# lipo_charger_sense_nicolai.net
KiCad netlist of a schematic drawn in EAGLE
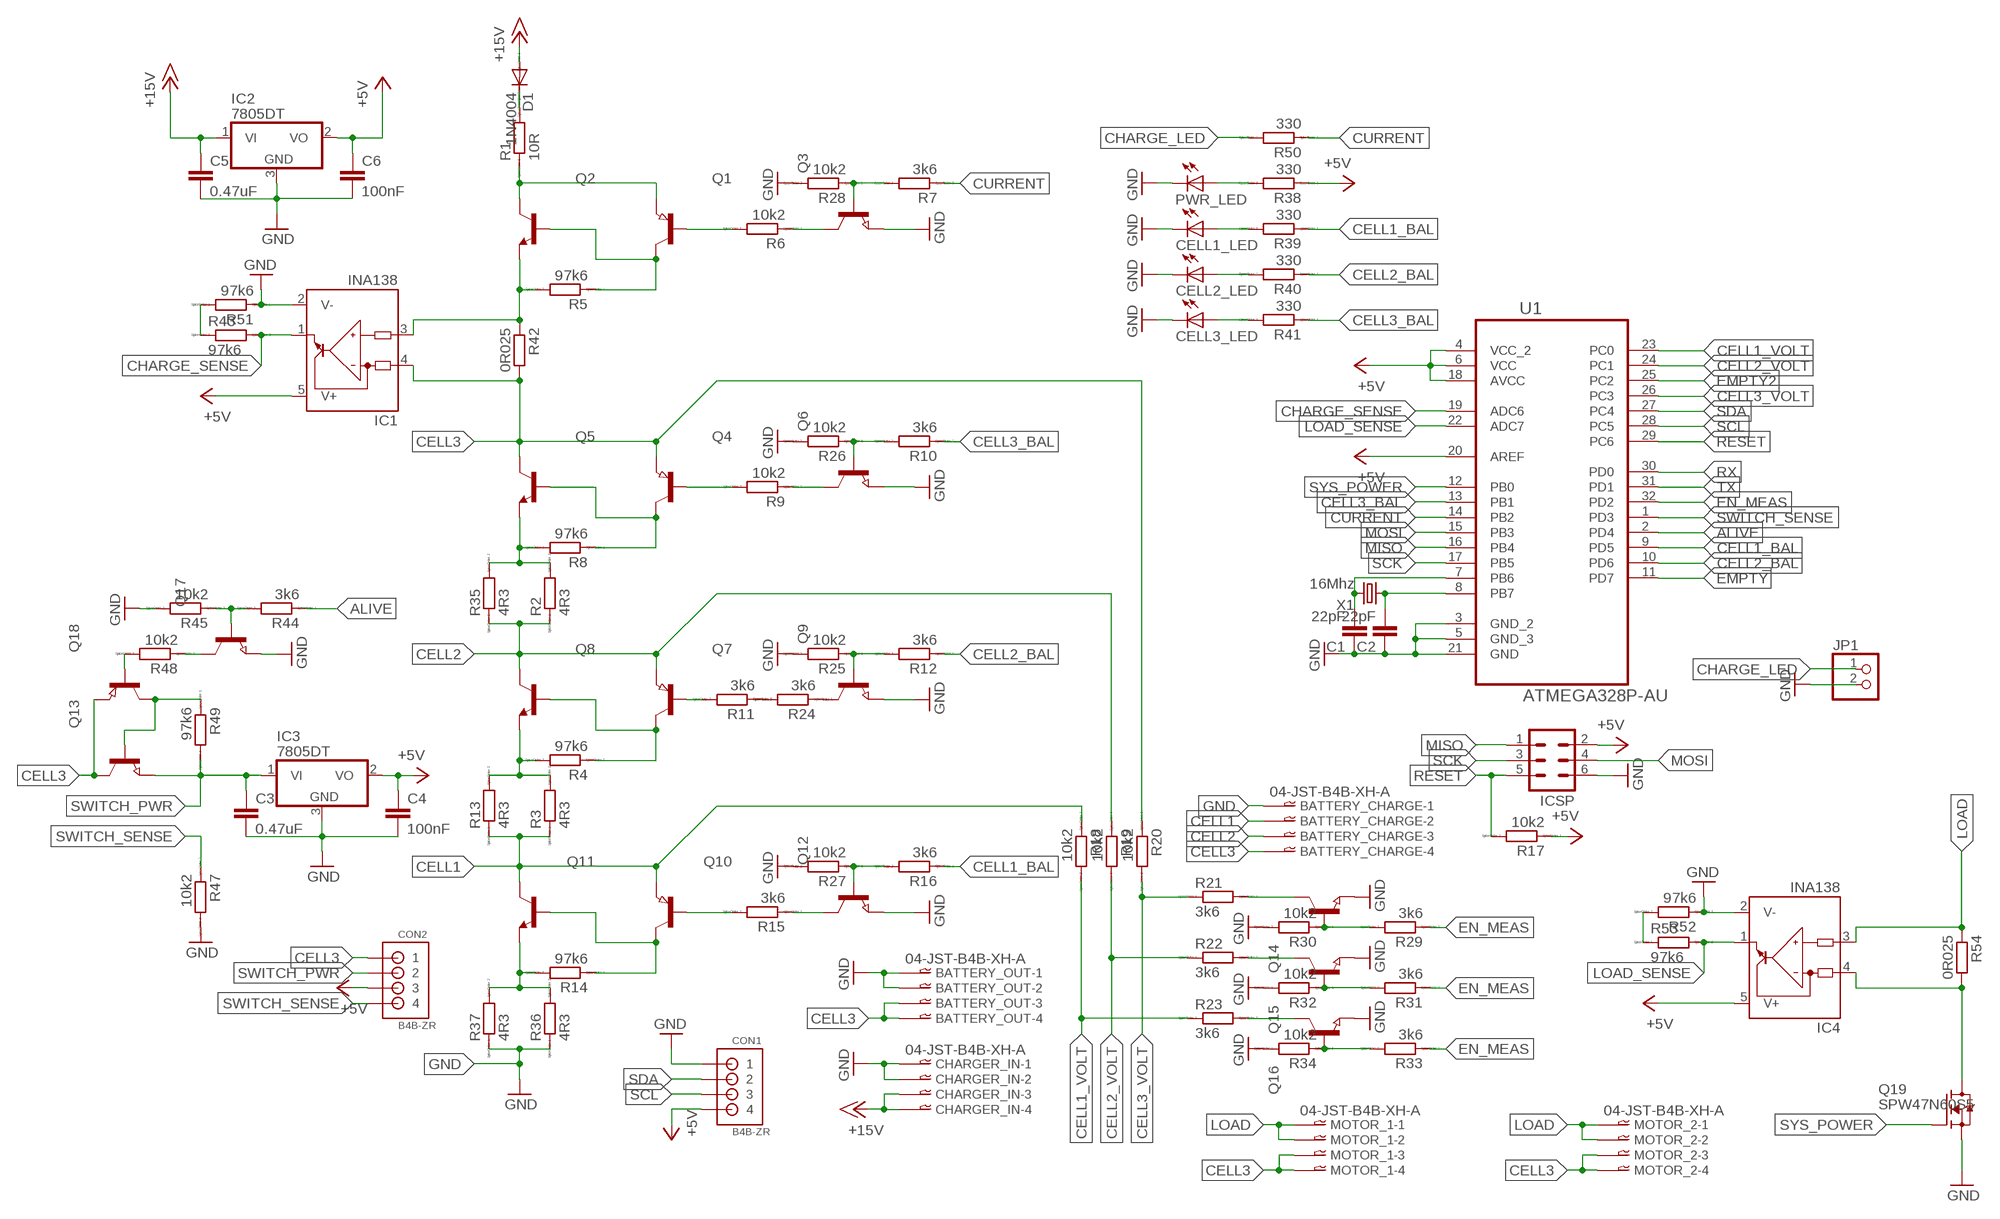
[diagram p0: schematic, sheet 1]

(export (version "E")
  (design (tool "Eeschema 10.0.6"))
  (components
    (comp (ref "BATTERY_CHARGE")
      (value "04-JST-B4B-XH-A")
      (footprint "eagle-import:B4B-XH")
      (libsource (lib "eagle-import") (part "04-JST-B4B-XH-A"))
    )
    (comp (ref "BATTERY_OUT")
      (value "04-JST-B4B-XH-A")
      (footprint "eagle-import:B4B-XH")
      (libsource (lib "eagle-import") (part "04-JST-B4B-XH-A"))
    )
    (comp (ref "C1")
      (value "22pF")
      (footprint "eagle-import:C0805K")
      (libsource (lib "eagle-import") (part "C-EUC0805K"))
    )
    (comp (ref "C2")
      (value "22pF")
      (footprint "eagle-import:C0805K")
      (libsource (lib "eagle-import") (part "C-EUC0805K"))
    )
    (comp (ref "C3")
      (value "0.47uF")
      (footprint "eagle-import:C0805K")
      (libsource (lib "eagle-import") (part "C-EUC0805K"))
    )
    (comp (ref "C4")
      (value "100nF")
      (footprint "eagle-import:C0805K")
      (libsource (lib "eagle-import") (part "C-EUC0805K"))
    )
    (comp (ref "C5")
      (value "0.47uF")
      (footprint "eagle-import:C0805K")
      (libsource (lib "eagle-import") (part "C-EUC0805K"))
    )
    (comp (ref "C6")
      (value "100nF")
      (footprint "eagle-import:C0805K")
      (libsource (lib "eagle-import") (part "C-EUC0805K"))
    )
    (comp (ref "CELL1_LED")
      (value "LEDSMT1206")
      (footprint "eagle-import:1206")
      (libsource (lib "eagle-import") (part "LEDSMT1206"))
    )
    (comp (ref "CELL2_LED")
      (value "LEDSMT1206")
      (footprint "eagle-import:1206")
      (libsource (lib "eagle-import") (part "LEDSMT1206"))
    )
    (comp (ref "CELL3_LED")
      (value "LEDSMT1206")
      (footprint "eagle-import:1206")
      (libsource (lib "eagle-import") (part "LEDSMT1206"))
    )
    (comp (ref "CHARGER_IN")
      (value "04-JST-B4B-XH-A")
      (footprint "eagle-import:B4B-XH")
      (libsource (lib "eagle-import") (part "04-JST-B4B-XH-A"))
    )
    (comp (ref "CON1")
      (value "B4B-ZR")
      (footprint "eagle-import:B4B-ZR")
      (libsource (lib "eagle-import") (part "B4B-ZR"))
    )
    (comp (ref "CON2")
      (value "B4B-ZR")
      (footprint "eagle-import:B4B-ZR")
      (libsource (lib "eagle-import") (part "B4B-ZR"))
    )
    (comp (ref "D1")
      (value "1N4004")
      (footprint "eagle-import:DO41-10")
      (libsource (lib "eagle-import") (part "1N4004"))
    )
    (comp (ref "IC1")
      (value "INA138")
      (footprint "eagle-import:SOT23-5")
      (fields (field (name "MF") "TEXAS INSTRUMENTS") (field (name "MPN") "INA138NA/250"))
      (libsource (lib "eagle-import") (part "INA138"))
    )
    (comp (ref "IC2")
      (value "7805DT")
      (footprint "eagle-import:TO252")
      (libsource (lib "eagle-import") (part "78DT05"))
    )
    (comp (ref "IC3")
      (value "7805DT")
      (footprint "eagle-import:TO252")
      (libsource (lib "eagle-import") (part "78DT05"))
    )
    (comp (ref "IC4")
      (value "INA138")
      (footprint "eagle-import:SOT23-5")
      (fields (field (name "MF") "TEXAS INSTRUMENTS") (field (name "MPN") "INA138NA/250"))
      (libsource (lib "eagle-import") (part "INA138"))
    )
    (comp (ref "ICSP")
      (value "MA03-2")
      (footprint "eagle-import:MA03-2")
      (libsource (lib "eagle-import") (part "MA03-2"))
    )
    (comp (ref "JP1")
      (value "PINHD-1X2/90")
      (footprint "eagle-import:1X02_90")
      (libsource (lib "eagle-import") (part "PINHD-1X2/90"))
    )
    (comp (ref "MOTOR_1")
      (value "04-JST-B4B-XH-A")
      (footprint "eagle-import:B4B-XH")
      (libsource (lib "eagle-import") (part "04-JST-B4B-XH-A"))
    )
    (comp (ref "MOTOR_2")
      (value "04-JST-B4B-XH-A")
      (footprint "eagle-import:B4B-XH")
      (libsource (lib "eagle-import") (part "04-JST-B4B-XH-A"))
    )
    (comp (ref "PWR_LED")
      (value "LEDSMT1206")
      (footprint "eagle-import:1206")
      (libsource (lib "eagle-import") (part "LEDSMT1206"))
    )
    (comp (ref "Q1")
      (value "PNP-TRANSISTOR_SOT23")
      (footprint "eagle-import:SOT23")
      (libsource (lib "eagle-import") (part "PNP-TRANSISTOR_SOT23"))
    )
    (comp (ref "Q2")
      (value "-NPN-")
      (footprint "eagle-import:DPAK")
      (libsource (lib "eagle-import") (part "-NPN-"))
    )
    (comp (ref "Q3")
      (value "NPN-TRANSISTOR_SOT23")
      (footprint "eagle-import:SOT23")
      (libsource (lib "eagle-import") (part "NPN-TRANSISTOR_SOT23"))
    )
    (comp (ref "Q4")
      (value "PNP-TRANSISTOR_SOT23")
      (footprint "eagle-import:SOT23")
      (libsource (lib "eagle-import") (part "PNP-TRANSISTOR_SOT23"))
    )
    (comp (ref "Q5")
      (value "-NPN-")
      (footprint "eagle-import:DPAK")
      (libsource (lib "eagle-import") (part "-NPN-"))
    )
    (comp (ref "Q6")
      (value "NPN-TRANSISTOR_SOT23")
      (footprint "eagle-import:SOT23")
      (libsource (lib "eagle-import") (part "NPN-TRANSISTOR_SOT23"))
    )
    (comp (ref "Q7")
      (value "PNP-TRANSISTOR_SOT23")
      (footprint "eagle-import:SOT23")
      (libsource (lib "eagle-import") (part "PNP-TRANSISTOR_SOT23"))
    )
    (comp (ref "Q8")
      (value "-NPN-")
      (footprint "eagle-import:DPAK")
      (libsource (lib "eagle-import") (part "-NPN-"))
    )
    (comp (ref "Q9")
      (value "NPN-TRANSISTOR_SOT23")
      (footprint "eagle-import:SOT23")
      (libsource (lib "eagle-import") (part "NPN-TRANSISTOR_SOT23"))
    )
    (comp (ref "Q10")
      (value "PNP-TRANSISTOR_SOT23")
      (footprint "eagle-import:SOT23")
      (libsource (lib "eagle-import") (part "PNP-TRANSISTOR_SOT23"))
    )
    (comp (ref "Q11")
      (value "-NPN-")
      (footprint "eagle-import:DPAK")
      (libsource (lib "eagle-import") (part "-NPN-"))
    )
    (comp (ref "Q12")
      (value "NPN-TRANSISTOR_SOT23")
      (footprint "eagle-import:SOT23")
      (libsource (lib "eagle-import") (part "NPN-TRANSISTOR_SOT23"))
    )
    (comp (ref "Q13")
      (value "NPN-TRANSISTOR_SOT23")
      (footprint "eagle-import:SOT23")
      (libsource (lib "eagle-import") (part "NPN-TRANSISTOR_SOT23"))
    )
    (comp (ref "Q14")
      (value "NPN-TRANSISTOR_SOT23")
      (footprint "eagle-import:SOT23")
      (libsource (lib "eagle-import") (part "NPN-TRANSISTOR_SOT23"))
    )
    (comp (ref "Q15")
      (value "NPN-TRANSISTOR_SOT23")
      (footprint "eagle-import:SOT23")
      (libsource (lib "eagle-import") (part "NPN-TRANSISTOR_SOT23"))
    )
    (comp (ref "Q16")
      (value "NPN-TRANSISTOR_SOT23")
      (footprint "eagle-import:SOT23")
      (libsource (lib "eagle-import") (part "NPN-TRANSISTOR_SOT23"))
    )
    (comp (ref "Q17")
      (value "NPN-TRANSISTOR_SOT23")
      (footprint "eagle-import:SOT23")
      (libsource (lib "eagle-import") (part "NPN-TRANSISTOR_SOT23"))
    )
    (comp (ref "Q18")
      (value "PNP-TRANSISTOR_SOT23")
      (footprint "eagle-import:SOT23")
      (libsource (lib "eagle-import") (part "PNP-TRANSISTOR_SOT23"))
    )
    (comp (ref "Q19")
      (value "SPW47N60S5")
      (footprint "eagle-import:DPACK_2")
      (libsource (lib "eagle-import") (part "SPW47N60S5"))
    )
    (comp (ref "R1")
      (value "10R")
      (footprint "eagle-import:SMW5")
      (libsource (lib "eagle-import") (part "R-EU_SMW5"))
    )
    (comp (ref "R2")
      (value "4R3")
      (footprint "eagle-import:SMW5")
      (libsource (lib "eagle-import") (part "R-EU_SMW5"))
    )
    (comp (ref "R3")
      (value "4R3")
      (footprint "eagle-import:SMW5")
      (libsource (lib "eagle-import") (part "R-EU_SMW5"))
    )
    (comp (ref "R4")
      (value "97k6")
      (footprint "eagle-import:R0805")
      (libsource (lib "eagle-import") (part "resistor_R-EU_R0805"))
    )
    (comp (ref "R5")
      (value "97k6")
      (footprint "eagle-import:R0805")
      (libsource (lib "eagle-import") (part "resistor_R-EU_R0805"))
    )
    (comp (ref "R6")
      (value "10k2")
      (footprint "eagle-import:R0805")
      (libsource (lib "eagle-import") (part "resistor_R-EU_R0805"))
    )
    (comp (ref "R7")
      (value "3k6")
      (footprint "eagle-import:R0805")
      (libsource (lib "eagle-import") (part "resistor_R-EU_R0805"))
    )
    (comp (ref "R8")
      (value "97k6")
      (footprint "eagle-import:R0805")
      (libsource (lib "eagle-import") (part "resistor_R-EU_R0805"))
    )
    (comp (ref "R9")
      (value "10k2")
      (footprint "eagle-import:R0805")
      (libsource (lib "eagle-import") (part "resistor_R-EU_R0805"))
    )
    (comp (ref "R10")
      (value "3k6")
      (footprint "eagle-import:R0805")
      (libsource (lib "eagle-import") (part "resistor_R-EU_R0805"))
    )
    (comp (ref "R11")
      (value "3k6")
      (footprint "eagle-import:R0805")
      (libsource (lib "eagle-import") (part "resistor_R-EU_R0805"))
    )
    (comp (ref "R12")
      (value "3k6")
      (footprint "eagle-import:R0805")
      (libsource (lib "eagle-import") (part "resistor_R-EU_R0805"))
    )
    (comp (ref "R13")
      (value "4R3")
      (footprint "eagle-import:SMW5")
      (libsource (lib "eagle-import") (part "R-EU_SMW5"))
    )
    (comp (ref "R14")
      (value "97k6")
      (footprint "eagle-import:R0805")
      (libsource (lib "eagle-import") (part "resistor_R-EU_R0805"))
    )
    (comp (ref "R15")
      (value "3k6")
      (footprint "eagle-import:R0805")
      (libsource (lib "eagle-import") (part "resistor_R-EU_R0805"))
    )
    (comp (ref "R16")
      (value "3k6")
      (footprint "eagle-import:R0805")
      (libsource (lib "eagle-import") (part "resistor_R-EU_R0805"))
    )
    (comp (ref "R17")
      (value "10k2")
      (footprint "eagle-import:R0805")
      (libsource (lib "eagle-import") (part "resistor_R-EU_R0805"))
    )
    (comp (ref "R18")
      (value "10k2")
      (footprint "eagle-import:R0805")
      (libsource (lib "eagle-import") (part "resistor_R-EU_R0805"))
    )
    (comp (ref "R19")
      (value "10k2")
      (footprint "eagle-import:R0805")
      (libsource (lib "eagle-import") (part "resistor_R-EU_R0805"))
    )
    (comp (ref "R20")
      (value "10k2")
      (footprint "eagle-import:R0805")
      (libsource (lib "eagle-import") (part "resistor_R-EU_R0805"))
    )
    (comp (ref "R21")
      (value "3k6")
      (footprint "eagle-import:R0805")
      (libsource (lib "eagle-import") (part "resistor_R-EU_R0805"))
    )
    (comp (ref "R22")
      (value "3k6")
      (footprint "eagle-import:R0805")
      (libsource (lib "eagle-import") (part "resistor_R-EU_R0805"))
    )
    (comp (ref "R23")
      (value "3k6")
      (footprint "eagle-import:R0805")
      (libsource (lib "eagle-import") (part "resistor_R-EU_R0805"))
    )
    (comp (ref "R24")
      (value "3k6")
      (footprint "eagle-import:R0805")
      (libsource (lib "eagle-import") (part "resistor_R-EU_R0805"))
    )
    (comp (ref "R25")
      (value "10k2")
      (footprint "eagle-import:R0805")
      (libsource (lib "eagle-import") (part "resistor_R-EU_R0805"))
    )
    (comp (ref "R26")
      (value "10k2")
      (footprint "eagle-import:R0805")
      (libsource (lib "eagle-import") (part "resistor_R-EU_R0805"))
    )
    (comp (ref "R27")
      (value "10k2")
      (footprint "eagle-import:R0805")
      (libsource (lib "eagle-import") (part "resistor_R-EU_R0805"))
    )
    (comp (ref "R28")
      (value "10k2")
      (footprint "eagle-import:R0805")
      (libsource (lib "eagle-import") (part "resistor_R-EU_R0805"))
    )
    (comp (ref "R29")
      (value "3k6")
      (footprint "eagle-import:R0805")
      (libsource (lib "eagle-import") (part "resistor_R-EU_R0805"))
    )
    (comp (ref "R30")
      (value "10k2")
      (footprint "eagle-import:R0805")
      (libsource (lib "eagle-import") (part "resistor_R-EU_R0805"))
    )
    (comp (ref "R31")
      (value "3k6")
      (footprint "eagle-import:R0805")
      (libsource (lib "eagle-import") (part "resistor_R-EU_R0805"))
    )
    (comp (ref "R32")
      (value "10k2")
      (footprint "eagle-import:R0805")
      (libsource (lib "eagle-import") (part "resistor_R-EU_R0805"))
    )
    (comp (ref "R33")
      (value "3k6")
      (footprint "eagle-import:R0805")
      (libsource (lib "eagle-import") (part "resistor_R-EU_R0805"))
    )
    (comp (ref "R34")
      (value "10k2")
      (footprint "eagle-import:R0805")
      (libsource (lib "eagle-import") (part "resistor_R-EU_R0805"))
    )
    (comp (ref "R35")
      (value "4R3")
      (footprint "eagle-import:SMW5")
      (libsource (lib "eagle-import") (part "R-EU_SMW5"))
    )
    (comp (ref "R36")
      (value "4R3")
      (footprint "eagle-import:SMW5")
      (libsource (lib "eagle-import") (part "R-EU_SMW5"))
    )
    (comp (ref "R37")
      (value "4R3")
      (footprint "eagle-import:SMW5")
      (libsource (lib "eagle-import") (part "R-EU_SMW5"))
    )
    (comp (ref "R38")
      (value "330")
      (footprint "eagle-import:R0805")
      (libsource (lib "eagle-import") (part "resistor_R-EU_R0805"))
    )
    (comp (ref "R39")
      (value "330")
      (footprint "eagle-import:R0805")
      (libsource (lib "eagle-import") (part "resistor_R-EU_R0805"))
    )
    (comp (ref "R40")
      (value "330")
      (footprint "eagle-import:R0805")
      (libsource (lib "eagle-import") (part "resistor_R-EU_R0805"))
    )
    (comp (ref "R41")
      (value "330")
      (footprint "eagle-import:R0805")
      (libsource (lib "eagle-import") (part "resistor_R-EU_R0805"))
    )
    (comp (ref "R42")
      (value "0R025")
      (footprint "eagle-import:R2512")
      (libsource (lib "eagle-import") (part "R-EU_R2512"))
    )
    (comp (ref "R43")
      (value "97k6")
      (footprint "eagle-import:R0805")
      (libsource (lib "eagle-import") (part "resistor_R-EU_R0805"))
    )
    (comp (ref "R44")
      (value "3k6")
      (footprint "eagle-import:R0805")
      (libsource (lib "eagle-import") (part "resistor_R-EU_R0805"))
    )
    (comp (ref "R45")
      (value "10k2")
      (footprint "eagle-import:R0805")
      (libsource (lib "eagle-import") (part "resistor_R-EU_R0805"))
    )
    (comp (ref "R47")
      (value "10k2")
      (footprint "eagle-import:R0805")
      (libsource (lib "eagle-import") (part "resistor_R-EU_R0805"))
    )
    (comp (ref "R48")
      (value "10k2")
      (footprint "eagle-import:R0805")
      (libsource (lib "eagle-import") (part "resistor_R-EU_R0805"))
    )
    (comp (ref "R49")
      (value "97k6")
      (footprint "eagle-import:R0805")
      (libsource (lib "eagle-import") (part "resistor_R-EU_R0805"))
    )
    (comp (ref "R50")
      (value "330")
      (footprint "eagle-import:R0805")
      (libsource (lib "eagle-import") (part "resistor_R-EU_R0805"))
    )
    (comp (ref "R51")
      (value "97k6")
      (footprint "eagle-import:R0805")
      (libsource (lib "eagle-import") (part "resistor_R-EU_R0805"))
    )
    (comp (ref "R52")
      (value "97k6")
      (footprint "eagle-import:R0805")
      (libsource (lib "eagle-import") (part "resistor_R-EU_R0805"))
    )
    (comp (ref "R53")
      (value "97k6")
      (footprint "eagle-import:R0805")
      (libsource (lib "eagle-import") (part "resistor_R-EU_R0805"))
    )
    (comp (ref "R54")
      (value "0R025")
      (footprint "eagle-import:R2512")
      (libsource (lib "eagle-import") (part "R-EU_R2512"))
    )
    (comp (ref "U1")
      (value "ATMEGA328P-AU")
      (footprint "eagle-import:QFP80P900X900X120-32N")
      (libsource (lib "eagle-import") (part "ATMEGA328P-AU"))
    )
    (comp (ref "X1")
      (value "16Mhz")
      (footprint "eagle-import:7.5X5-2-PAD")
      (libsource (lib "eagle-import") (part "CRYSTALS-NOGND-12SMX-A"))
    )
  )
  (nets
    (net (code "1") (name "+5V") (class "Default")
      (node (ref "C4") (pin "1") (pinfunction "1_1") (pintype "passive"))
      (node (ref "C6") (pin "1") (pinfunction "1_1") (pintype "passive"))
      (node (ref "CON1") (pin "4") (pinfunction "4_4") (pintype "bidirectional"))
      (node (ref "CON2") (pin "3") (pinfunction "3_3") (pintype "bidirectional"))
      (node (ref "IC1") (pin "5") (pinfunction "V+_5") (pintype "power_in"))
      (node (ref "IC2") (pin "2") (pinfunction "VO_2") (pintype "passive"))
      (node (ref "IC3") (pin "2") (pinfunction "VO_2") (pintype "passive"))
      (node (ref "IC4") (pin "5") (pinfunction "V+_5") (pintype "power_in"))
      (node (ref "ICSP") (pin "2") (pinfunction "2_2") (pintype "passive"))
      (node (ref "R17") (pin "1") (pinfunction "1_1") (pintype "passive"))
      (node (ref "R38") (pin "1") (pinfunction "1_1") (pintype "passive"))
      (node (ref "U1") (pin "18") (pinfunction "AVCC_18") (pintype "power_in"))
      (node (ref "U1") (pin "20") (pinfunction "AREF_20") (pintype "input"))
      (node (ref "U1") (pin "4") (pinfunction "VCC_2_4") (pintype "power_in"))
      (node (ref "U1") (pin "6") (pinfunction "VCC_6") (pintype "power_in"))
    )
    (net (code "2") (name "+15V") (class "Default")
      (node (ref "C5") (pin "1") (pinfunction "1_1") (pintype "passive"))
      (node (ref "CHARGER_IN") (pin "P$3") (pinfunction "1_P$3") (pintype "passive"))
      (node (ref "CHARGER_IN") (pin "P$4") (pinfunction "1_P$4") (pintype "passive"))
      (node (ref "D1") (pin "A") (pinfunction "A_A") (pintype "passive"))
      (node (ref "IC2") (pin "1") (pinfunction "VI_1") (pintype "input"))
    )
    (net (code "3") (name "ALIVE") (class "Default")
      (node (ref "R44") (pin "1") (pinfunction "1_1") (pintype "passive"))
      (node (ref "U1") (pin "2") (pinfunction "PD4_2") (pintype "bidirectional"))
    )
    (net (code "4") (name "CELL1") (class "Default")
      (node (ref "BATTERY_CHARGE") (pin "P$2") (pinfunction "1_P$2") (pintype "passive"))
      (node (ref "Q10") (pin "2") (pinfunction "E_2") (pintype "passive"))
      (node (ref "Q11") (pin "3") (pinfunction "C_3") (pintype "passive"))
      (node (ref "R13") (pin "P$1") (pinfunction "1_P$1") (pintype "passive"))
      (node (ref "R18") (pin "1") (pinfunction "1_1") (pintype "passive"))
      (node (ref "R3") (pin "P$1") (pinfunction "1_P$1") (pintype "passive"))
    )
    (net (code "5") (name "CELL1_BAL") (class "Default")
      (node (ref "R16") (pin "1") (pinfunction "1_1") (pintype "passive"))
      (node (ref "R39") (pin "1") (pinfunction "1_1") (pintype "passive"))
      (node (ref "U1") (pin "9") (pinfunction "PD5_9") (pintype "bidirectional"))
    )
    (net (code "6") (name "CELL1_VOLT") (class "Default")
      (node (ref "R18") (pin "2") (pinfunction "2_2") (pintype "passive"))
      (node (ref "R23") (pin "1") (pinfunction "1_1") (pintype "passive"))
      (node (ref "U1") (pin "23") (pinfunction "PC0_23") (pintype "bidirectional"))
    )
    (net (code "7") (name "CELL2") (class "Default")
      (node (ref "BATTERY_CHARGE") (pin "P$3") (pinfunction "1_P$3") (pintype "passive"))
      (node (ref "Q7") (pin "2") (pinfunction "E_2") (pintype "passive"))
      (node (ref "Q8") (pin "3") (pinfunction "C_3") (pintype "passive"))
      (node (ref "R19") (pin "1") (pinfunction "1_1") (pintype "passive"))
      (node (ref "R2") (pin "P$1") (pinfunction "1_P$1") (pintype "passive"))
      (node (ref "R35") (pin "P$1") (pinfunction "1_P$1") (pintype "passive"))
    )
    (net (code "8") (name "CELL2_BAL") (class "Default")
      (node (ref "R12") (pin "1") (pinfunction "1_1") (pintype "passive"))
      (node (ref "R40") (pin "1") (pinfunction "1_1") (pintype "passive"))
      (node (ref "U1") (pin "10") (pinfunction "PD6_10") (pintype "bidirectional"))
    )
    (net (code "9") (name "CELL2_VOLT") (class "Default")
      (node (ref "R19") (pin "2") (pinfunction "2_2") (pintype "passive"))
      (node (ref "R22") (pin "1") (pinfunction "1_1") (pintype "passive"))
      (node (ref "U1") (pin "24") (pinfunction "PC1_24") (pintype "bidirectional"))
    )
    (net (code "10") (name "CELL3") (class "Default")
      (node (ref "BATTERY_CHARGE") (pin "P$4") (pinfunction "1_P$4") (pintype "passive"))
      (node (ref "BATTERY_OUT") (pin "P$3") (pinfunction "1_P$3") (pintype "passive"))
      (node (ref "BATTERY_OUT") (pin "P$4") (pinfunction "1_P$4") (pintype "passive"))
      (node (ref "CON2") (pin "1") (pinfunction "1_1") (pintype "bidirectional"))
      (node (ref "IC1") (pin "4") (pinfunction "IN-_4") (pintype "input"))
      (node (ref "MOTOR_1") (pin "P$3") (pinfunction "1_P$3") (pintype "passive"))
      (node (ref "MOTOR_1") (pin "P$4") (pinfunction "1_P$4") (pintype "passive"))
      (node (ref "MOTOR_2") (pin "P$3") (pinfunction "1_P$3") (pintype "passive"))
      (node (ref "MOTOR_2") (pin "P$4") (pinfunction "1_P$4") (pintype "passive"))
      (node (ref "Q13") (pin "3") (pinfunction "C_3") (pintype "passive"))
      (node (ref "Q18") (pin "2") (pinfunction "E_2") (pintype "passive"))
      (node (ref "Q4") (pin "2") (pinfunction "E_2") (pintype "passive"))
      (node (ref "Q5") (pin "3") (pinfunction "C_3") (pintype "passive"))
      (node (ref "R20") (pin "1") (pinfunction "1_1") (pintype "passive"))
      (node (ref "R42") (pin "2") (pinfunction "2_2") (pintype "passive"))
    )
    (net (code "11") (name "CELL3_BAL") (class "Default")
      (node (ref "R10") (pin "1") (pinfunction "1_1") (pintype "passive"))
      (node (ref "R41") (pin "1") (pinfunction "1_1") (pintype "passive"))
      (node (ref "U1") (pin "13") (pinfunction "PB1_13") (pintype "bidirectional"))
    )
    (net (code "12") (name "CELL3_VOLT") (class "Default")
      (node (ref "R20") (pin "2") (pinfunction "2_2") (pintype "passive"))
      (node (ref "R21") (pin "1") (pinfunction "1_1") (pintype "passive"))
      (node (ref "U1") (pin "26") (pinfunction "PC3_26") (pintype "bidirectional"))
    )
    (net (code "13") (name "CHARGE_LED") (class "Default")
      (node (ref "JP1") (pin "1") (pinfunction "1_1") (pintype "passive"))
      (node (ref "R50") (pin "2") (pinfunction "2_2") (pintype "passive"))
    )
    (net (code "14") (name "CHARGE_SENSE") (class "Default")
      (node (ref "IC1") (pin "1") (pinfunction "OUT_1") (pintype "output"))
      (node (ref "R43") (pin "2") (pinfunction "2_2") (pintype "passive"))
      (node (ref "U1") (pin "19") (pinfunction "ADC6_19") (pintype "input"))
    )
    (net (code "15") (name "CURRENT") (class "Default")
      (node (ref "R50") (pin "1") (pinfunction "1_1") (pintype "passive"))
      (node (ref "R7") (pin "1") (pinfunction "1_1") (pintype "passive"))
      (node (ref "U1") (pin "14") (pinfunction "PB2_14") (pintype "bidirectional"))
    )
    (net (code "16") (name "EMPTY") (class "Default")
      (node (ref "U1") (pin "11") (pinfunction "PD7_11") (pintype "bidirectional"))
    )
    (net (code "17") (name "EMPTY2") (class "Default")
      (node (ref "U1") (pin "25") (pinfunction "PC2_25") (pintype "bidirectional"))
    )
    (net (code "18") (name "EN_MEAS") (class "Default")
      (node (ref "R29") (pin "1") (pinfunction "1_1") (pintype "passive"))
      (node (ref "R31") (pin "1") (pinfunction "1_1") (pintype "passive"))
      (node (ref "R33") (pin "1") (pinfunction "1_1") (pintype "passive"))
      (node (ref "U1") (pin "32") (pinfunction "PD2_32") (pintype "bidirectional"))
    )
    (net (code "19") (name "GND") (class "Default")
      (node (ref "BATTERY_CHARGE") (pin "P$1") (pinfunction "1_P$1") (pintype "passive"))
      (node (ref "BATTERY_OUT") (pin "P$1") (pinfunction "1_P$1") (pintype "passive"))
      (node (ref "BATTERY_OUT") (pin "P$2") (pinfunction "1_P$2") (pintype "passive"))
      (node (ref "C1") (pin "1") (pinfunction "1_1") (pintype "passive"))
      (node (ref "C2") (pin "1") (pinfunction "1_1") (pintype "passive"))
      (node (ref "C3") (pin "2") (pinfunction "2_2") (pintype "passive"))
      (node (ref "C4") (pin "2") (pinfunction "2_2") (pintype "passive"))
      (node (ref "C5") (pin "2") (pinfunction "2_2") (pintype "passive"))
      (node (ref "C6") (pin "2") (pinfunction "2_2") (pintype "passive"))
      (node (ref "CELL1_LED") (pin "C") (pinfunction "C_C") (pintype "passive"))
      (node (ref "CELL2_LED") (pin "C") (pinfunction "C_C") (pintype "passive"))
      (node (ref "CELL3_LED") (pin "C") (pinfunction "C_C") (pintype "passive"))
      (node (ref "CHARGER_IN") (pin "P$1") (pinfunction "1_P$1") (pintype "passive"))
      (node (ref "CHARGER_IN") (pin "P$2") (pinfunction "1_P$2") (pintype "passive"))
      (node (ref "CON1") (pin "1") (pinfunction "1_1") (pintype "bidirectional"))
      (node (ref "IC1") (pin "2") (pinfunction "V-_2") (pintype "power_in"))
      (node (ref "IC2") (pin "3") (pinfunction "GND_3") (pintype "passive"))
      (node (ref "IC3") (pin "3") (pinfunction "GND_3") (pintype "passive"))
      (node (ref "IC4") (pin "2") (pinfunction "V-_2") (pintype "power_in"))
      (node (ref "ICSP") (pin "6") (pinfunction "6_6") (pintype "passive"))
      (node (ref "JP1") (pin "2") (pinfunction "2_2") (pintype "passive"))
      (node (ref "PWR_LED") (pin "C") (pinfunction "C_C") (pintype "passive"))
      (node (ref "Q12") (pin "2") (pinfunction "E_2") (pintype "passive"))
      (node (ref "Q14") (pin "2") (pinfunction "E_2") (pintype "passive"))
      (node (ref "Q15") (pin "2") (pinfunction "E_2") (pintype "passive"))
      (node (ref "Q16") (pin "2") (pinfunction "E_2") (pintype "passive"))
      (node (ref "Q17") (pin "2") (pinfunction "E_2") (pintype "passive"))
      (node (ref "Q19") (pin "S") (pinfunction "S_S") (pintype "passive"))
      (node (ref "Q3") (pin "2") (pinfunction "E_2") (pintype "passive"))
      (node (ref "Q6") (pin "2") (pinfunction "E_2") (pintype "passive"))
      (node (ref "Q9") (pin "2") (pinfunction "E_2") (pintype "passive"))
      (node (ref "R25") (pin "2") (pinfunction "2_2") (pintype "passive"))
      (node (ref "R26") (pin "2") (pinfunction "2_2") (pintype "passive"))
      (node (ref "R27") (pin "2") (pinfunction "2_2") (pintype "passive"))
      (node (ref "R28") (pin "2") (pinfunction "2_2") (pintype "passive"))
      (node (ref "R30") (pin "2") (pinfunction "2_2") (pintype "passive"))
      (node (ref "R32") (pin "2") (pinfunction "2_2") (pintype "passive"))
      (node (ref "R34") (pin "2") (pinfunction "2_2") (pintype "passive"))
      (node (ref "R36") (pin "P$1") (pinfunction "1_P$1") (pintype "passive"))
      (node (ref "R37") (pin "P$1") (pinfunction "1_P$1") (pintype "passive"))
      (node (ref "R45") (pin "2") (pinfunction "2_2") (pintype "passive"))
      (node (ref "R47") (pin "2") (pinfunction "2_2") (pintype "passive"))
      (node (ref "R51") (pin "1") (pinfunction "1_1") (pintype "passive"))
      (node (ref "R52") (pin "1") (pinfunction "1_1") (pintype "passive"))
      (node (ref "U1") (pin "21") (pinfunction "GND_21") (pintype "passive"))
      (node (ref "U1") (pin "3") (pinfunction "GND_2_3") (pintype "passive"))
      (node (ref "U1") (pin "5") (pinfunction "GND_3_5") (pintype "passive"))
    )
    (net (code "20") (name "LOAD") (class "Default")
      (node (ref "IC4") (pin "3") (pinfunction "IN+_3") (pintype "input"))
      (node (ref "MOTOR_1") (pin "P$1") (pinfunction "1_P$1") (pintype "passive"))
      (node (ref "MOTOR_1") (pin "P$2") (pinfunction "1_P$2") (pintype "passive"))
      (node (ref "MOTOR_2") (pin "P$1") (pinfunction "1_P$1") (pintype "passive"))
      (node (ref "MOTOR_2") (pin "P$2") (pinfunction "1_P$2") (pintype "passive"))
      (node (ref "R54") (pin "1") (pinfunction "1_1") (pintype "passive"))
    )
    (net (code "21") (name "LOAD_SENSE") (class "Default")
      (node (ref "IC4") (pin "1") (pinfunction "OUT_1") (pintype "output"))
      (node (ref "R53") (pin "2") (pinfunction "2_2") (pintype "passive"))
      (node (ref "U1") (pin "22") (pinfunction "ADC7_22") (pintype "input"))
    )
    (net (code "22") (name "MISO") (class "Default")
      (node (ref "ICSP") (pin "1") (pinfunction "1_1") (pintype "passive"))
      (node (ref "U1") (pin "16") (pinfunction "PB4_16") (pintype "bidirectional"))
    )
    (net (code "23") (name "MOSI") (class "Default")
      (node (ref "ICSP") (pin "4") (pinfunction "4_4") (pintype "passive"))
      (node (ref "U1") (pin "15") (pinfunction "PB3_15") (pintype "bidirectional"))
    )
    (net (code "24") (name "Net-(CELL1_LED-PadA)") (class "Default")
      (node (ref "CELL1_LED") (pin "A") (pinfunction "A_A") (pintype "passive"))
      (node (ref "R39") (pin "2") (pinfunction "2_2") (pintype "passive"))
    )
    (net (code "25") (name "Net-(CELL2_LED-PadA)") (class "Default")
      (node (ref "CELL2_LED") (pin "A") (pinfunction "A_A") (pintype "passive"))
      (node (ref "R40") (pin "2") (pinfunction "2_2") (pintype "passive"))
    )
    (net (code "26") (name "Net-(CELL3_LED-PadA)") (class "Default")
      (node (ref "CELL3_LED") (pin "A") (pinfunction "A_A") (pintype "passive"))
      (node (ref "R41") (pin "2") (pinfunction "2_2") (pintype "passive"))
    )
    (net (code "27") (name "Net-(IC1-IN+)") (class "Default")
      (node (ref "IC1") (pin "3") (pinfunction "IN+_3") (pintype "input"))
      (node (ref "Q2") (pin "4") (pinfunction "E_4") (pintype "passive"))
      (node (ref "R42") (pin "1") (pinfunction "1_1") (pintype "passive"))
      (node (ref "R5") (pin "2") (pinfunction "2_2") (pintype "passive"))
    )
    (net (code "28") (name "Net-(IC4-IN-)") (class "Default")
      (node (ref "IC4") (pin "4") (pinfunction "IN-_4") (pintype "input"))
      (node (ref "Q19") (pin "D") (pinfunction "D_D") (pintype "passive"))
      (node (ref "R54") (pin "2") (pinfunction "2_2") (pintype "passive"))
    )
    (net (code "29") (name "Net-(PWR_LED-PadA)") (class "Default")
      (node (ref "PWR_LED") (pin "A") (pinfunction "A_A") (pintype "passive"))
      (node (ref "R38") (pin "2") (pinfunction "2_2") (pintype "passive"))
    )
    (net (code "30") (name "Net-(Q1-B)") (class "Default")
      (node (ref "Q1") (pin "1") (pinfunction "B_1") (pintype "passive"))
      (node (ref "R6") (pin "2") (pinfunction "2_2") (pintype "passive"))
    )
    (net (code "31") (name "Net-(Q1-C)") (class "Default")
      (node (ref "Q1") (pin "3") (pinfunction "C_3") (pintype "passive"))
      (node (ref "Q2") (pin "1") (pinfunction "B_1") (pintype "passive"))
      (node (ref "R5") (pin "1") (pinfunction "1_1") (pintype "passive"))
    )
    (net (code "32") (name "Net-(Q1-E)") (class "Default")
      (node (ref "Q1") (pin "2") (pinfunction "E_2") (pintype "passive"))
      (node (ref "Q2") (pin "3") (pinfunction "C_3") (pintype "passive"))
      (node (ref "R1") (pin "P$1") (pinfunction "1_P$1") (pintype "passive"))
    )
    (net (code "33") (name "Net-(Q3-B)") (class "Default")
      (node (ref "Q3") (pin "1") (pinfunction "B_1") (pintype "passive"))
      (node (ref "R28") (pin "1") (pinfunction "1_1") (pintype "passive"))
      (node (ref "R7") (pin "2") (pinfunction "2_2") (pintype "passive"))
    )
    (net (code "34") (name "Net-(Q3-C)") (class "Default")
      (node (ref "Q3") (pin "3") (pinfunction "C_3") (pintype "passive"))
      (node (ref "R6") (pin "1") (pinfunction "1_1") (pintype "passive"))
    )
    (net (code "35") (name "Net-(Q4-B)") (class "Default")
      (node (ref "Q4") (pin "1") (pinfunction "B_1") (pintype "passive"))
      (node (ref "R9") (pin "2") (pinfunction "2_2") (pintype "passive"))
    )
    (net (code "36") (name "Net-(Q4-C)") (class "Default")
      (node (ref "Q4") (pin "3") (pinfunction "C_3") (pintype "passive"))
      (node (ref "Q5") (pin "1") (pinfunction "B_1") (pintype "passive"))
      (node (ref "R8") (pin "1") (pinfunction "1_1") (pintype "passive"))
    )
    (net (code "37") (name "Net-(Q5-E)") (class "Default")
      (node (ref "Q5") (pin "4") (pinfunction "E_4") (pintype "passive"))
      (node (ref "R2") (pin "P$2") (pinfunction "2_P$2") (pintype "passive"))
      (node (ref "R35") (pin "P$2") (pinfunction "2_P$2") (pintype "passive"))
      (node (ref "R8") (pin "2") (pinfunction "2_2") (pintype "passive"))
    )
    (net (code "38") (name "Net-(Q6-B)") (class "Default")
      (node (ref "Q6") (pin "1") (pinfunction "B_1") (pintype "passive"))
      (node (ref "R10") (pin "2") (pinfunction "2_2") (pintype "passive"))
      (node (ref "R26") (pin "1") (pinfunction "1_1") (pintype "passive"))
    )
    (net (code "39") (name "Net-(Q6-C)") (class "Default")
      (node (ref "Q6") (pin "3") (pinfunction "C_3") (pintype "passive"))
      (node (ref "R9") (pin "1") (pinfunction "1_1") (pintype "passive"))
    )
    (net (code "40") (name "Net-(Q7-B)") (class "Default")
      (node (ref "Q7") (pin "1") (pinfunction "B_1") (pintype "passive"))
      (node (ref "R11") (pin "2") (pinfunction "2_2") (pintype "passive"))
    )
    (net (code "41") (name "Net-(Q7-C)") (class "Default")
      (node (ref "Q7") (pin "3") (pinfunction "C_3") (pintype "passive"))
      (node (ref "Q8") (pin "1") (pinfunction "B_1") (pintype "passive"))
      (node (ref "R4") (pin "1") (pinfunction "1_1") (pintype "passive"))
    )
    (net (code "42") (name "Net-(Q8-E)") (class "Default")
      (node (ref "Q8") (pin "4") (pinfunction "E_4") (pintype "passive"))
      (node (ref "R13") (pin "P$2") (pinfunction "2_P$2") (pintype "passive"))
      (node (ref "R3") (pin "P$2") (pinfunction "2_P$2") (pintype "passive"))
      (node (ref "R4") (pin "2") (pinfunction "2_2") (pintype "passive"))
    )
    (net (code "43") (name "Net-(Q9-B)") (class "Default")
      (node (ref "Q9") (pin "1") (pinfunction "B_1") (pintype "passive"))
      (node (ref "R12") (pin "2") (pinfunction "2_2") (pintype "passive"))
      (node (ref "R25") (pin "1") (pinfunction "1_1") (pintype "passive"))
    )
    (net (code "44") (name "Net-(Q9-C)") (class "Default")
      (node (ref "Q9") (pin "3") (pinfunction "C_3") (pintype "passive"))
      (node (ref "R24") (pin "1") (pinfunction "1_1") (pintype "passive"))
    )
    (net (code "45") (name "Net-(Q10-B)") (class "Default")
      (node (ref "Q10") (pin "1") (pinfunction "B_1") (pintype "passive"))
      (node (ref "R15") (pin "2") (pinfunction "2_2") (pintype "passive"))
    )
    (net (code "46") (name "Net-(Q10-C)") (class "Default")
      (node (ref "Q10") (pin "3") (pinfunction "C_3") (pintype "passive"))
      (node (ref "Q11") (pin "1") (pinfunction "B_1") (pintype "passive"))
      (node (ref "R14") (pin "1") (pinfunction "1_1") (pintype "passive"))
    )
    (net (code "47") (name "Net-(Q11-E)") (class "Default")
      (node (ref "Q11") (pin "4") (pinfunction "E_4") (pintype "passive"))
      (node (ref "R14") (pin "2") (pinfunction "2_2") (pintype "passive"))
      (node (ref "R36") (pin "P$2") (pinfunction "2_P$2") (pintype "passive"))
      (node (ref "R37") (pin "P$2") (pinfunction "2_P$2") (pintype "passive"))
    )
    (net (code "48") (name "Net-(Q12-B)") (class "Default")
      (node (ref "Q12") (pin "1") (pinfunction "B_1") (pintype "passive"))
      (node (ref "R16") (pin "2") (pinfunction "2_2") (pintype "passive"))
      (node (ref "R27") (pin "1") (pinfunction "1_1") (pintype "passive"))
    )
    (net (code "49") (name "Net-(Q12-C)") (class "Default")
      (node (ref "Q12") (pin "3") (pinfunction "C_3") (pintype "passive"))
      (node (ref "R15") (pin "1") (pinfunction "1_1") (pintype "passive"))
    )
    (net (code "50") (name "Net-(Q13-B)") (class "Default")
      (node (ref "Q13") (pin "1") (pinfunction "B_1") (pintype "passive"))
      (node (ref "Q18") (pin "3") (pinfunction "C_3") (pintype "passive"))
      (node (ref "R49") (pin "1") (pinfunction "1_1") (pintype "passive"))
    )
    (net (code "51") (name "Net-(Q14-B)") (class "Default")
      (node (ref "Q14") (pin "1") (pinfunction "B_1") (pintype "passive"))
      (node (ref "R29") (pin "2") (pinfunction "2_2") (pintype "passive"))
      (node (ref "R30") (pin "1") (pinfunction "1_1") (pintype "passive"))
    )
    (net (code "52") (name "Net-(Q14-C)") (class "Default")
      (node (ref "Q14") (pin "3") (pinfunction "C_3") (pintype "passive"))
      (node (ref "R21") (pin "2") (pinfunction "2_2") (pintype "passive"))
    )
    (net (code "53") (name "Net-(Q15-B)") (class "Default")
      (node (ref "Q15") (pin "1") (pinfunction "B_1") (pintype "passive"))
      (node (ref "R31") (pin "2") (pinfunction "2_2") (pintype "passive"))
      (node (ref "R32") (pin "1") (pinfunction "1_1") (pintype "passive"))
    )
    (net (code "54") (name "Net-(Q15-C)") (class "Default")
      (node (ref "Q15") (pin "3") (pinfunction "C_3") (pintype "passive"))
      (node (ref "R22") (pin "2") (pinfunction "2_2") (pintype "passive"))
    )
    (net (code "55") (name "Net-(Q16-B)") (class "Default")
      (node (ref "Q16") (pin "1") (pinfunction "B_1") (pintype "passive"))
      (node (ref "R33") (pin "2") (pinfunction "2_2") (pintype "passive"))
      (node (ref "R34") (pin "1") (pinfunction "1_1") (pintype "passive"))
    )
    (net (code "56") (name "Net-(Q16-C)") (class "Default")
      (node (ref "Q16") (pin "3") (pinfunction "C_3") (pintype "passive"))
      (node (ref "R23") (pin "2") (pinfunction "2_2") (pintype "passive"))
    )
    (net (code "57") (name "Net-(Q17-B)") (class "Default")
      (node (ref "Q17") (pin "1") (pinfunction "B_1") (pintype "passive"))
      (node (ref "R44") (pin "2") (pinfunction "2_2") (pintype "passive"))
      (node (ref "R45") (pin "1") (pinfunction "1_1") (pintype "passive"))
    )
    (net (code "58") (name "Net-(Q17-C)") (class "Default")
      (node (ref "Q17") (pin "3") (pinfunction "C_3") (pintype "passive"))
      (node (ref "R48") (pin "1") (pinfunction "1_1") (pintype "passive"))
    )
    (net (code "59") (name "Net-(Q18-B)") (class "Default")
      (node (ref "Q18") (pin "1") (pinfunction "B_1") (pintype "passive"))
      (node (ref "R48") (pin "2") (pinfunction "2_2") (pintype "passive"))
    )
    (net (code "60") (name "Net-(R1-2)") (class "Default")
      (node (ref "D1") (pin "C") (pinfunction "C_C") (pintype "passive"))
      (node (ref "R1") (pin "P$2") (pinfunction "2_P$2") (pintype "passive"))
    )
    (net (code "61") (name "Net-(R11-Pad1)") (class "Default")
      (node (ref "R11") (pin "1") (pinfunction "1_1") (pintype "passive"))
      (node (ref "R24") (pin "2") (pinfunction "2_2") (pintype "passive"))
    )
    (net (code "62") (name "Net-(R43-Pad1)") (class "Default")
      (node (ref "R43") (pin "1") (pinfunction "1_1") (pintype "passive"))
      (node (ref "R51") (pin "2") (pinfunction "2_2") (pintype "passive"))
    )
    (net (code "63") (name "Net-(R52-Pad2)") (class "Default")
      (node (ref "R52") (pin "2") (pinfunction "2_2") (pintype "passive"))
      (node (ref "R53") (pin "1") (pinfunction "1_1") (pintype "passive"))
    )
    (net (code "64") (name "Net-(U1-PB6)") (class "Default")
      (node (ref "C1") (pin "2") (pinfunction "2_2") (pintype "passive"))
      (node (ref "U1") (pin "7") (pinfunction "PB6_7") (pintype "bidirectional"))
      (node (ref "X1") (pin "2") (pinfunction "2_2") (pintype "passive"))
    )
    (net (code "65") (name "Net-(U1-PB7)") (class "Default")
      (node (ref "C2") (pin "2") (pinfunction "2_2") (pintype "passive"))
      (node (ref "U1") (pin "8") (pinfunction "PB7_8") (pintype "bidirectional"))
      (node (ref "X1") (pin "1") (pinfunction "1_1") (pintype "passive"))
    )
    (net (code "66") (name "RESET") (class "Default")
      (node (ref "ICSP") (pin "5") (pinfunction "5_5") (pintype "passive"))
      (node (ref "R17") (pin "2") (pinfunction "2_2") (pintype "passive"))
      (node (ref "U1") (pin "29") (pinfunction "PC6_29") (pintype "bidirectional"))
    )
    (net (code "67") (name "RX") (class "Default")
      (node (ref "U1") (pin "30") (pinfunction "PD0_30") (pintype "bidirectional"))
    )
    (net (code "68") (name "SCK") (class "Default")
      (node (ref "ICSP") (pin "3") (pinfunction "3_3") (pintype "passive"))
      (node (ref "U1") (pin "17") (pinfunction "PB5_17") (pintype "bidirectional"))
    )
    (net (code "69") (name "SCL") (class "Default")
      (node (ref "CON1") (pin "3") (pinfunction "3_3") (pintype "bidirectional"))
      (node (ref "U1") (pin "28") (pinfunction "PC5_28") (pintype "bidirectional"))
    )
    (net (code "70") (name "SDA") (class "Default")
      (node (ref "CON1") (pin "2") (pinfunction "2_2") (pintype "bidirectional"))
      (node (ref "U1") (pin "27") (pinfunction "PC4_27") (pintype "bidirectional"))
    )
    (net (code "71") (name "SWITCH_PWR") (class "Default")
      (node (ref "C3") (pin "1") (pinfunction "1_1") (pintype "passive"))
      (node (ref "CON2") (pin "2") (pinfunction "2_2") (pintype "bidirectional"))
      (node (ref "IC3") (pin "1") (pinfunction "VI_1") (pintype "input"))
      (node (ref "Q13") (pin "2") (pinfunction "E_2") (pintype "passive"))
      (node (ref "R49") (pin "2") (pinfunction "2_2") (pintype "passive"))
    )
    (net (code "72") (name "SWITCH_SENSE") (class "Default")
      (node (ref "CON2") (pin "4") (pinfunction "4_4") (pintype "bidirectional"))
      (node (ref "R47") (pin "1") (pinfunction "1_1") (pintype "passive"))
      (node (ref "U1") (pin "1") (pinfunction "PD3_1") (pintype "bidirectional"))
    )
    (net (code "73") (name "SYS_POWER") (class "Default")
      (node (ref "Q19") (pin "G") (pinfunction "G_G") (pintype "passive"))
      (node (ref "U1") (pin "12") (pinfunction "PB0_12") (pintype "bidirectional"))
    )
    (net (code "74") (name "TX") (class "Default")
      (node (ref "U1") (pin "31") (pinfunction "PD1_31") (pintype "bidirectional"))
    )
  )
)
